# 32minboard.net
KiCad netlist of a schematic drawn in Altium Designer
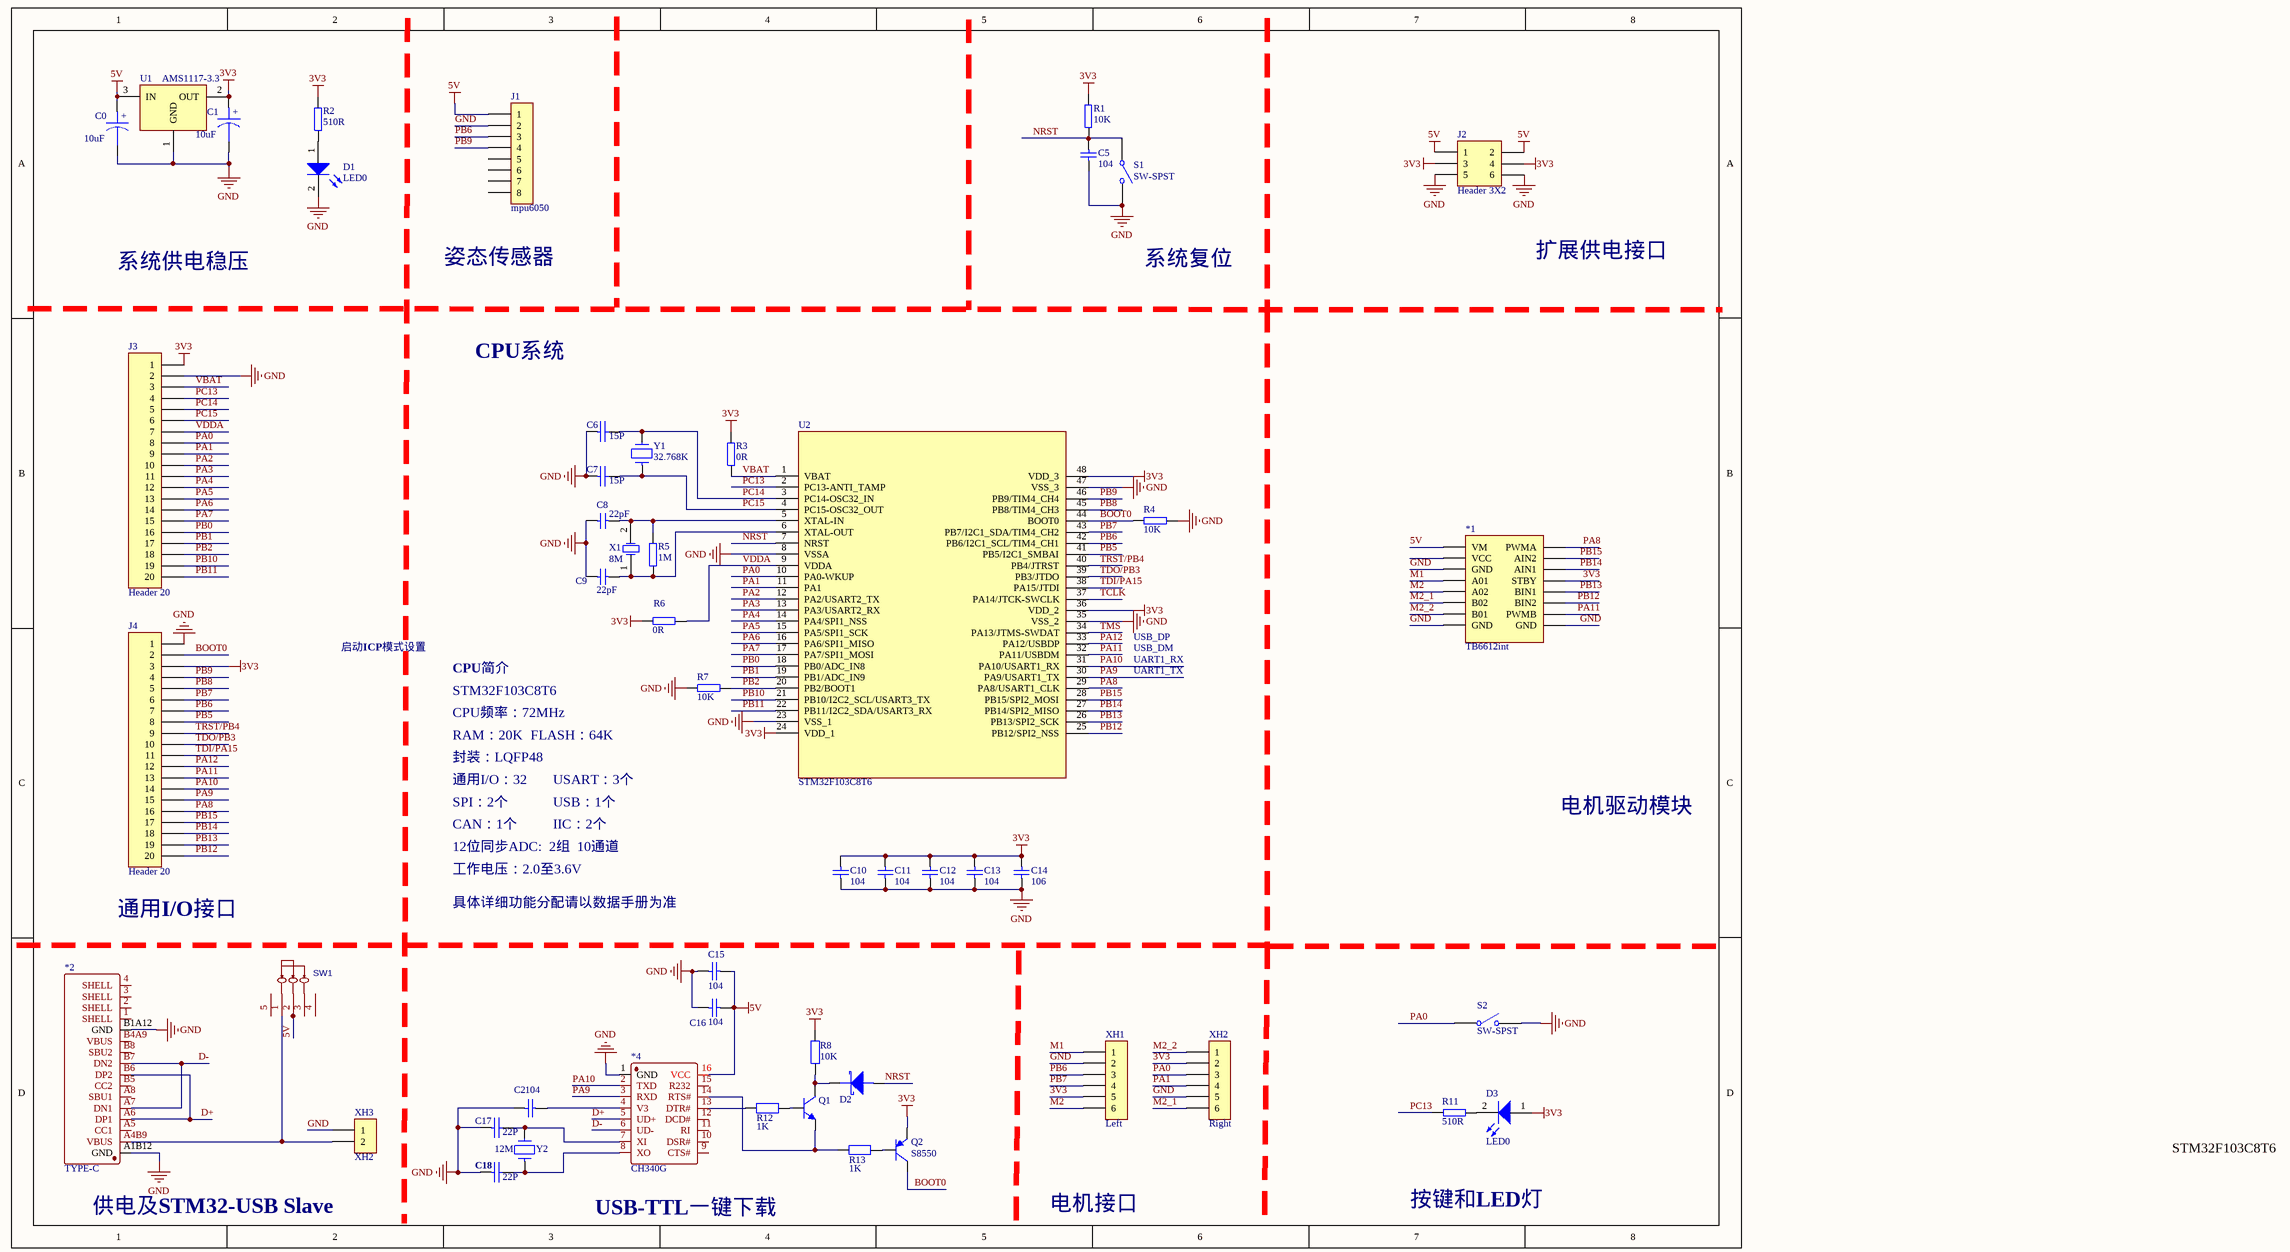
[diagram p0: 32minboard.SchDoc]

(export (version "E")
  (design (tool "Eeschema 10.0.6"))
  (components
    (comp (ref "*1")
      (value "TB6612int")
      (footprint "TB6612int")
      (libsource (lib "General") (part "TB6612int"))
    )
    (comp (ref "*2") (value "TYPE-C") (footprint "TYPE-C") (libsource (lib "General") (part "TYPE-C")))
    (comp (ref "*4")
      (value "CH340G")
      (footprint "SOIC-16_L9.9-W3.9-P1.27-LS6.0-BR")
      (libsource (lib "General") (part "CH340G"))
    )
    (comp (ref "C0")
      (value "10uF")
      (footprint "CAP-TANTALUM-A")
      (description "Capacitor")
      (libsource (lib "*") (part "CAPACITOR POL"))
    )
    (comp (ref "C1")
      (value "10uF")
      (footprint "CAP-TANTALUM-A")
      (description "Capacitor")
      (libsource (lib "*") (part "CAPACITOR POL"))
    )
    (comp (ref "C2")
      (value "104")
      (footprint "0603")
      (description "Capacitor")
      (libsource (lib "Miscellaneous Devices") (part "Cap"))
    )
    (comp (ref "C5")
      (value "104")
      (footprint "0603")
      (description "Capacitor")
      (fields (field (name "PUBLISHER") "ZL_A0OFFICE"))
      (libsource (lib "CommomDevices") (part "CAP1"))
    )
    (comp (ref "C6") (value "15P") (footprint "0603") (libsource (lib "*") (part "CAP")))
    (comp (ref "C7") (value "15P") (footprint "0603") (libsource (lib "*") (part "CAP")))
    (comp (ref "C8")
      (value "22pF")
      (footprint "0603")
      (description "Capacitor")
      (fields (field (name "PUBLISHER") "ZL_A0OFFICE"))
      (libsource (lib "CommomDevices") (part "CAP1"))
    )
    (comp (ref "C9")
      (value "22pF")
      (footprint "0603")
      (description "Capacitor")
      (fields (field (name "PUBLISHER") "ZL_A0OFFICE"))
      (libsource (lib "CommomDevices") (part "CAP1"))
    )
    (comp (ref "C10")
      (value "104")
      (footprint "0603")
      (description "Capacitor")
      (fields (field (name "PUBLISHER") "ZL_A0OFFICE"))
      (libsource (lib "CommomDevices") (part "CAP1"))
    )
    (comp (ref "C11")
      (value "104")
      (footprint "0603")
      (description "Capacitor")
      (fields (field (name "PUBLISHER") "ZL_A0OFFICE"))
      (libsource (lib "CommomDevices") (part "CAP1"))
    )
    (comp (ref "C12")
      (value "104")
      (footprint "0603")
      (description "Capacitor")
      (fields (field (name "PUBLISHER") "ZL_A0OFFICE"))
      (libsource (lib "CommomDevices") (part "CAP1"))
    )
    (comp (ref "C13")
      (value "104")
      (footprint "0603")
      (description "Capacitor")
      (fields (field (name "PUBLISHER") "ZL_A0OFFICE"))
      (libsource (lib "CommomDevices") (part "CAP1"))
    )
    (comp (ref "C14")
      (value "106")
      (footprint "0603")
      (description "Capacitor")
      (fields (field (name "PUBLISHER") "ZL_A0OFFICE"))
      (libsource (lib "CommomDevices") (part "CAP1"))
    )
    (comp (ref "C15")
      (value "104")
      (footprint "0603")
      (description "Capacitor")
      (libsource (lib "Miscellaneous Devices") (part "Cap"))
    )
    (comp (ref "C16")
      (value "104")
      (footprint "0603")
      (description "Capacitor")
      (libsource (lib "Miscellaneous Devices") (part "Cap"))
    )
    (comp (ref "C17") (value "22P") (footprint "0603") (libsource (lib "*") (part "CAP")))
    (comp (ref "C18") (value "22P") (footprint "0603") (libsource (lib "*") (part "CAP")))
    (comp (ref "D1")
      (value "LED0")
      (footprint "LED-0805")
      (description "Typical INFRARED GaAs LED")
      (libsource (lib "Miscellaneous Devices") (part "LED0"))
    )
    (comp (ref "D2")
      (value "DIODE SCHOTTKY")
      (footprint "LL34")
      (description "肖特基二极管")
      (libsource (lib "二极管") (part "DIODE SCHOTTKY"))
    )
    (comp (ref "D3")
      (value "LED0")
      (footprint "LED-0805")
      (description "Typical INFRARED GaAs LED")
      (libsource (lib "Miscellaneous Devices") (part "LED0"))
    )
    (comp (ref "J1")
      (value "mpu6050")
      (footprint "PIN-8-2.54-1.0")
      (description "Connector")
      (libsource (lib "General") (part "HDR1x8"))
    )
    (comp (ref "J2")
      (value "Header 3X2")
      (footprint "PIN-2x3-2.54-1.0")
      (description "Header, 3-Pin, Dual row")
      (fields (field (name "PUBLISHER") "Altium Limited"))
      (libsource (lib "Miscellaneous Connectors") (part "Header 3X2"))
    )
    (comp (ref "J3")
      (value "Header 20")
      (footprint "PIN-20-2.54-1.0")
      (description "Header, 20-Pin")
      (fields (field (name "PUBLISHER") "Altium Limited"))
      (libsource (lib "Miscellaneous Connectors") (part "Header 20"))
    )
    (comp (ref "J4")
      (value "Header 20")
      (footprint "PIN-20-2.54-1.0")
      (description "Header, 20-Pin")
      (fields (field (name "PUBLISHER") "Altium Limited"))
      (libsource (lib "Miscellaneous Connectors") (part "Header 20"))
    )
    (comp (ref "Q1")
      (value "MMBT2222A")
      (footprint "SOT-23")
      (description "NPN Bipolar Transistor")
      (libsource (lib "General") (part "MMBT2222A"))
    )
    (comp (ref "Q2")
      (value "S8550")
      (footprint "SOT-23")
      (description "NPN Bipolar Transistor")
      (libsource (lib "General") (part "PNP"))
    )
    (comp (ref "R1") (value "10K") (footprint "0603") (libsource (lib "ZIBO V2.0_Main") (part "R")))
    (comp (ref "R2") (value "510R") (footprint "0603") (libsource (lib "ZIBO V2.0_Main") (part "R")))
    (comp (ref "R3") (value "0R") (footprint "0603") (libsource (lib "ZIBO V2.0_Main") (part "R")))
    (comp (ref "R4") (value "10K") (footprint "0603") (libsource (lib "ZIBO V2.0_Main") (part "R")))
    (comp (ref "R5") (value "1M") (footprint "0603") (libsource (lib "ZIBO V2.0_Main") (part "R")))
    (comp (ref "R6") (value "0R") (footprint "0603") (libsource (lib "ZIBO V2.0_Main") (part "R")))
    (comp (ref "R7") (value "10K") (footprint "0603") (libsource (lib "ZIBO V2.0_Main") (part "R")))
    (comp (ref "R8")
      (value "10K")
      (footprint "0603")
      (description "Resistor")
      (libsource (lib "") (part "Res2_1"))
    )
    (comp (ref "R11") (value "510R") (footprint "0603") (libsource (lib "ZIBO V2.0_Main") (part "R")))
    (comp (ref "R12")
      (value "1K")
      (footprint "0603")
      (description "Resistor")
      (libsource (lib "Miscellaneous Devices") (part "Res2"))
    )
    (comp (ref "R13")
      (value "1K")
      (footprint "0603")
      (description "Resistor")
      (libsource (lib "Miscellaneous Devices") (part "Res2"))
    )
    (comp (ref "S1")
      (value "SW-SPST")
      (footprint "KEY-SWD-3X4X2")
      (description "Single-Pole, Single-Throw Switch")
      (libsource (lib "Miscellaneous Devices") (part "SW-SPST"))
    )
    (comp (ref "S2")
      (value "SW-SPST")
      (footprint "KEY-SWD-3X4X2")
      (description "Single-Pole, Single-Throw Switch")
      (libsource (lib "Miscellaneous Devices") (part "SW-SPST"))
    )
    (comp (ref "SW1")
      (value "SK12D07VG5")
      (footprint "SW-TH_SK12D07VG5")
      (fields (field (name "BOM_SUPPLIER PART") "C431548") (field (name "CONTRIBUTOR") "LCSC"))
      (libsource (lib "General") (part "SK12D07VG5"))
    )
    (comp (ref "U1")
      (value "AMS1117-3.3")
      (footprint "SOT223")
      (libsource (lib "Newcapec9263_Board_NEW") (part "LT1085CM-3.3"))
    )
    (comp (ref "U2")
      (value "STM32F103C8T6")
      (footprint "QFP-48-0.5")
      (libsource (lib "STM32_Smart") (part "STM32F103C8T6"))
    )
    (comp (ref "X1")
      (value "8M")
      (footprint "OSC HC-49SMD")
      (description "Crystal Oscillator")
      (fields (field (name "PUBLISHER") "ZL_A0OFFICE"))
      (libsource (lib "CommomDevices") (part "XTAL_SMD"))
    )
    (comp (ref "XH1") (value "Left") (footprint "XH6/2.54mm/180") (libsource (lib "XH，VH") (part "XH6")))
    (comp (ref "XH2") (value "Right") (footprint "XH6/2.54mm/180") (libsource (lib "XH，VH") (part "XH6")))
    (comp (ref "XH3") (value "XH2") (footprint "XH2/2.54mm/180") (libsource (lib "XH，VH") (part "XH2")))
    (comp (ref "Y1")
      (value "32.768K")
      (footprint "OSC-3x8-WI-B")
      (description "晶振")
      (libsource (lib "*") (part "CRYSTAL"))
    )
    (comp (ref "Y2")
      (value "12M")
      (footprint "OSC HC-49SMD")
      (description "晶振")
      (libsource (lib "*") (part "CRYSTAL"))
    )
  )
  (nets
    (net (code "1") (name "/BOOT0") (class "Default")
      (node (ref "J4") (pin "2") (pinfunction "2_2") (pintype "passive"))
      (node (ref "Q2") (pin "2") (pinfunction "C_2") (pintype "passive"))
      (node (ref "R4") (pin "2") (pinfunction "2_2") (pintype "passive"))
      (node (ref "U2") (pin "44") (pinfunction "BOOT0_44") (pintype "passive"))
    )
    (net (code "2") (name "/D+") (class "Default")
      (node (ref "*2") (pin "A6") (pinfunction "DP1_A6") (pintype "passive"))
      (node (ref "*2") (pin "B6") (pinfunction "DP2_B6") (pintype "passive"))
      (node (ref "*4") (pin "5") (pinfunction "UD+_5") (pintype "passive"))
    )
    (net (code "3") (name "/D-") (class "Default")
      (node (ref "*2") (pin "A7") (pinfunction "DN1_A7") (pintype "passive"))
      (node (ref "*2") (pin "B7") (pinfunction "DN2_B7") (pintype "passive"))
      (node (ref "*4") (pin "6") (pinfunction "UD-_6") (pintype "passive"))
    )
    (net (code "4") (name "/M1") (class "Default")
      (node (ref "*1") (pin "4") (pinfunction "A01_4") (pintype "passive"))
      (node (ref "XH1") (pin "1") (pinfunction "1_1") (pintype "passive"))
    )
    (net (code "5") (name "/M2") (class "Default")
      (node (ref "*1") (pin "5") (pinfunction "A02_5") (pintype "passive"))
      (node (ref "XH1") (pin "6") (pinfunction "6_6") (pintype "passive"))
    )
    (net (code "6") (name "/M2_1") (class "Default")
      (node (ref "*1") (pin "6") (pinfunction "B02_6") (pintype "passive"))
      (node (ref "XH2") (pin "6") (pinfunction "6_6") (pintype "passive"))
    )
    (net (code "7") (name "/M2_2") (class "Default")
      (node (ref "*1") (pin "7") (pinfunction "B01_7") (pintype "passive"))
      (node (ref "XH2") (pin "1") (pinfunction "1_1") (pintype "passive"))
    )
    (net (code "8") (name "/NRST") (class "Default")
      (node (ref "C5") (pin "1") (pinfunction "1_1") (pintype "passive"))
      (node (ref "D2") (pin "A") (pinfunction "A_A") (pintype "passive"))
      (node (ref "R1") (pin "1") (pinfunction "1_1") (pintype "passive"))
      (node (ref "S1") (pin "1") (pinfunction "COMMON_1") (pintype "passive"))
      (node (ref "U2") (pin "7") (pinfunction "NRST_7") (pintype "passive"))
    )
    (net (code "9") (name "/PA0") (class "Default")
      (node (ref "J3") (pin "8") (pinfunction "8_8") (pintype "passive"))
      (node (ref "S2") (pin "1") (pinfunction "COMMON_1") (pintype "passive"))
      (node (ref "U2") (pin "10") (pinfunction "PA0-WKUP_10") (pintype "passive"))
      (node (ref "XH2") (pin "3") (pinfunction "3_3") (pintype "passive"))
    )
    (net (code "10") (name "/PA1") (class "Default")
      (node (ref "J3") (pin "9") (pinfunction "9_9") (pintype "passive"))
      (node (ref "U2") (pin "11") (pinfunction "PA1_11") (pintype "passive"))
      (node (ref "XH2") (pin "4") (pinfunction "4_4") (pintype "passive"))
    )
    (net (code "11") (name "/PA2") (class "Default")
      (node (ref "J3") (pin "10") (pinfunction "10_10") (pintype "passive"))
      (node (ref "U2") (pin "12") (pinfunction "PA2/USART2_TX_12") (pintype "passive"))
    )
    (net (code "12") (name "/PA3") (class "Default")
      (node (ref "J3") (pin "11") (pinfunction "11_11") (pintype "passive"))
      (node (ref "U2") (pin "13") (pinfunction "PA3/USART2_RX_13") (pintype "passive"))
    )
    (net (code "13") (name "/PA4") (class "Default")
      (node (ref "J3") (pin "12") (pinfunction "12_12") (pintype "passive"))
      (node (ref "U2") (pin "14") (pinfunction "PA4/SPI1_NSS_14") (pintype "passive"))
    )
    (net (code "14") (name "/PA5") (class "Default")
      (node (ref "J3") (pin "13") (pinfunction "13_13") (pintype "passive"))
      (node (ref "U2") (pin "15") (pinfunction "PA5/SPI1_SCK_15") (pintype "passive"))
    )
    (net (code "15") (name "/PA6") (class "Default")
      (node (ref "J3") (pin "14") (pinfunction "14_14") (pintype "passive"))
      (node (ref "U2") (pin "16") (pinfunction "PA6/SPI1_MISO_16") (pintype "passive"))
    )
    (net (code "16") (name "/PA7") (class "Default")
      (node (ref "J3") (pin "15") (pinfunction "15_15") (pintype "passive"))
      (node (ref "U2") (pin "17") (pinfunction "PA7/SPI1_MOSI_17") (pintype "passive"))
    )
    (net (code "17") (name "/PA8") (class "Default")
      (node (ref "*1") (pin "16") (pinfunction "PWMA_16") (pintype "passive"))
      (node (ref "J4") (pin "16") (pinfunction "16_16") (pintype "passive"))
      (node (ref "U2") (pin "29") (pinfunction "PA8/USART1_CLK_29") (pintype "passive"))
    )
    (net (code "18") (name "/PA9") (class "Default")
      (node (ref "*4") (pin "3") (pinfunction "RXD_3") (pintype "passive"))
      (node (ref "J4") (pin "15") (pinfunction "15_15") (pintype "passive"))
      (node (ref "U2") (pin "30") (pinfunction "PA9/USART1_TX_30") (pintype "passive"))
    )
    (net (code "19") (name "/PA10") (class "Default")
      (node (ref "*4") (pin "2") (pinfunction "TXD_2") (pintype "passive"))
      (node (ref "J4") (pin "14") (pinfunction "14_14") (pintype "passive"))
      (node (ref "U2") (pin "31") (pinfunction "PA10/USART1_RX_31") (pintype "passive"))
    )
    (net (code "20") (name "/PA11") (class "Default")
      (node (ref "*1") (pin "10") (pinfunction "PWMB_10") (pintype "passive"))
      (node (ref "J4") (pin "13") (pinfunction "13_13") (pintype "passive"))
      (node (ref "U2") (pin "32") (pinfunction "PA11/USBDM_32") (pintype "passive"))
    )
    (net (code "21") (name "/PA12") (class "Default")
      (node (ref "J4") (pin "12") (pinfunction "12_12") (pintype "passive"))
      (node (ref "U2") (pin "33") (pinfunction "PA12/USBDP_33") (pintype "passive"))
    )
    (net (code "22") (name "/PB0") (class "Default")
      (node (ref "J3") (pin "16") (pinfunction "16_16") (pintype "passive"))
      (node (ref "U2") (pin "18") (pinfunction "PB0/ADC_IN8_18") (pintype "passive"))
    )
    (net (code "23") (name "/PB1") (class "Default")
      (node (ref "J3") (pin "17") (pinfunction "17_17") (pintype "passive"))
      (node (ref "U2") (pin "19") (pinfunction "PB1/ADC_IN9_19") (pintype "passive"))
    )
    (net (code "24") (name "/PB2") (class "Default")
      (node (ref "J3") (pin "18") (pinfunction "18_18") (pintype "passive"))
      (node (ref "R7") (pin "1") (pinfunction "1_1") (pintype "passive"))
      (node (ref "U2") (pin "20") (pinfunction "PB2/BOOT1_20") (pintype "passive"))
    )
    (net (code "25") (name "/PB5") (class "Default")
      (node (ref "J4") (pin "8") (pinfunction "8_8") (pintype "passive"))
      (node (ref "U2") (pin "41") (pinfunction "PB5/I2C1_SMBAI_41") (pintype "passive"))
    )
    (net (code "26") (name "/PB6") (class "Default")
      (node (ref "J1") (pin "3") (pinfunction "3_3") (pintype "passive"))
      (node (ref "J4") (pin "7") (pinfunction "7_7") (pintype "passive"))
      (node (ref "U2") (pin "42") (pinfunction "PB6/I2C1_SCL/TIM4_CH1_42") (pintype "passive"))
      (node (ref "XH1") (pin "3") (pinfunction "3_3") (pintype "passive"))
    )
    (net (code "27") (name "/PB7") (class "Default")
      (node (ref "J4") (pin "6") (pinfunction "6_6") (pintype "passive"))
      (node (ref "U2") (pin "43") (pinfunction "PB7/I2C1_SDA/TIM4_CH2_43") (pintype "passive"))
      (node (ref "XH1") (pin "4") (pinfunction "4_4") (pintype "passive"))
    )
    (net (code "28") (name "/PB8") (class "Default")
      (node (ref "J4") (pin "5") (pinfunction "5_5") (pintype "passive"))
      (node (ref "U2") (pin "45") (pinfunction "PB8/TIM4_CH3_45") (pintype "passive"))
    )
    (net (code "29") (name "/PB9") (class "Default")
      (node (ref "J1") (pin "4") (pinfunction "4_4") (pintype "passive"))
      (node (ref "J4") (pin "4") (pinfunction "4_4") (pintype "passive"))
      (node (ref "U2") (pin "46") (pinfunction "PB9/TIM4_CH4_46") (pintype "passive"))
    )
    (net (code "30") (name "/PB10") (class "Default")
      (node (ref "J3") (pin "19") (pinfunction "19_19") (pintype "passive"))
      (node (ref "U2") (pin "21") (pinfunction "PB10/I2C2_SCL/USART3_TX_21") (pintype "passive"))
    )
    (net (code "31") (name "/PB11") (class "Default")
      (node (ref "J3") (pin "20") (pinfunction "20_20") (pintype "passive"))
      (node (ref "U2") (pin "22") (pinfunction "PB11/I2C2_SDA/USART3_RX_22") (pintype "passive"))
    )
    (net (code "32") (name "/PB12") (class "Default")
      (node (ref "*1") (pin "11") (pinfunction "BIN2_11") (pintype "passive"))
      (node (ref "J4") (pin "20") (pinfunction "20_20") (pintype "passive"))
      (node (ref "U2") (pin "25") (pinfunction "PB12/SPI2_NSS_25") (pintype "passive"))
    )
    (net (code "33") (name "/PB13") (class "Default")
      (node (ref "*1") (pin "12") (pinfunction "BIN1_12") (pintype "passive"))
      (node (ref "J4") (pin "19") (pinfunction "19_19") (pintype "passive"))
      (node (ref "U2") (pin "26") (pinfunction "PB13/SPI2_SCK_26") (pintype "passive"))
    )
    (net (code "34") (name "/PB14") (class "Default")
      (node (ref "*1") (pin "14") (pinfunction "AIN1_14") (pintype "passive"))
      (node (ref "J4") (pin "18") (pinfunction "18_18") (pintype "passive"))
      (node (ref "U2") (pin "27") (pinfunction "PB14/SPI2_MISO_27") (pintype "passive"))
    )
    (net (code "35") (name "/PB15") (class "Default")
      (node (ref "*1") (pin "15") (pinfunction "AIN2_15") (pintype "passive"))
      (node (ref "J4") (pin "17") (pinfunction "17_17") (pintype "passive"))
      (node (ref "U2") (pin "28") (pinfunction "PB15/SPI2_MOSI_28") (pintype "passive"))
    )
    (net (code "36") (name "/PC13") (class "Default")
      (node (ref "J3") (pin "4") (pinfunction "4_4") (pintype "passive"))
      (node (ref "R11") (pin "1") (pinfunction "1_1") (pintype "passive"))
      (node (ref "U2") (pin "2") (pinfunction "PC13-ANTI_TAMP_2") (pintype "passive"))
    )
    (net (code "37") (name "/PC14") (class "Default")
      (node (ref "C6") (pin "2") (pintype "passive"))
      (node (ref "J3") (pin "5") (pinfunction "5_5") (pintype "passive"))
      (node (ref "U2") (pin "3") (pinfunction "PC14-OSC32_IN_3") (pintype "passive"))
      (node (ref "Y1") (pin "2") (pintype "passive"))
    )
    (net (code "38") (name "/PC15") (class "Default")
      (node (ref "C7") (pin "2") (pintype "passive"))
      (node (ref "J3") (pin "6") (pinfunction "6_6") (pintype "passive"))
      (node (ref "U2") (pin "4") (pinfunction "PC15-OSC32_OUT_4") (pintype "passive"))
      (node (ref "Y1") (pin "1") (pintype "passive"))
    )
    (net (code "39") (name "/TCLK") (class "Default")
      (node (ref "U2") (pin "37") (pinfunction "PA14/JTCK-SWCLK_37") (pintype "passive"))
    )
    (net (code "40") (name "/TDI{slash}PA15") (class "Default")
      (node (ref "J4") (pin "11") (pinfunction "11_11") (pintype "passive"))
      (node (ref "U2") (pin "38") (pinfunction "PA15/JTDI_38") (pintype "passive"))
    )
    (net (code "41") (name "/TDO{slash}PB3") (class "Default")
      (node (ref "J4") (pin "10") (pinfunction "10_10") (pintype "passive"))
      (node (ref "U2") (pin "39") (pinfunction "PB3/JTDO_39") (pintype "passive"))
    )
    (net (code "42") (name "/TMS") (class "Default")
      (node (ref "U2") (pin "34") (pinfunction "PA13/JTMS-SWDAT_34") (pintype "passive"))
    )
    (net (code "43") (name "/TRST{slash}PB4") (class "Default")
      (node (ref "J4") (pin "9") (pinfunction "9_9") (pintype "passive"))
      (node (ref "U2") (pin "40") (pinfunction "PB4/JTRST_40") (pintype "passive"))
    )
    (net (code "44") (name "/VBAT") (class "Default")
      (node (ref "J3") (pin "3") (pinfunction "3_3") (pintype "passive"))
      (node (ref "R3") (pin "1") (pinfunction "1_1") (pintype "passive"))
      (node (ref "U2") (pin "1") (pinfunction "VBAT_1") (pintype "passive"))
    )
    (net (code "45") (name "/VDDA") (class "Default")
      (node (ref "J3") (pin "7") (pinfunction "7_7") (pintype "passive"))
      (node (ref "R6") (pin "1") (pinfunction "1_1") (pintype "passive"))
      (node (ref "U2") (pin "9") (pinfunction "VDDA_9") (pintype "passive"))
    )
    (net (code "46") (name "3V3") (class "Default")
      (node (ref "*1") (pin "13") (pinfunction "STBY_13") (pintype "passive"))
      (node (ref "C1") (pin "1") (pinfunction "1_1") (pintype "passive"))
      (node (ref "C10") (pin "1") (pinfunction "1_1") (pintype "passive"))
      (node (ref "C11") (pin "1") (pinfunction "1_1") (pintype "passive"))
      (node (ref "C12") (pin "1") (pinfunction "1_1") (pintype "passive"))
      (node (ref "C13") (pin "1") (pinfunction "1_1") (pintype "passive"))
      (node (ref "C14") (pin "1") (pinfunction "1_1") (pintype "passive"))
      (node (ref "D3") (pin "1") (pinfunction "A_1") (pintype "passive"))
      (node (ref "J2") (pin "3") (pinfunction "3_3") (pintype "passive"))
      (node (ref "J2") (pin "4") (pinfunction "4_4") (pintype "passive"))
      (node (ref "J3") (pin "1") (pinfunction "1_1") (pintype "passive"))
      (node (ref "J4") (pin "3") (pinfunction "3_3") (pintype "passive"))
      (node (ref "Q2") (pin "3") (pinfunction "E_3") (pintype "passive"))
      (node (ref "R1") (pin "2") (pinfunction "2_2") (pintype "passive"))
      (node (ref "R2") (pin "2") (pinfunction "2_2") (pintype "passive"))
      (node (ref "R3") (pin "2") (pinfunction "2_2") (pintype "passive"))
      (node (ref "R6") (pin "2") (pinfunction "2_2") (pintype "passive"))
      (node (ref "R8") (pin "1") (pinfunction "1_1") (pintype "passive"))
      (node (ref "U1") (pin "2") (pinfunction "OUT_2") (pintype "passive"))
      (node (ref "U2") (pin "24") (pinfunction "VDD_1_24") (pintype "passive"))
      (node (ref "U2") (pin "36") (pinfunction "VDD_2_36") (pintype "passive"))
      (node (ref "U2") (pin "48") (pinfunction "VDD_3_48") (pintype "passive"))
      (node (ref "XH1") (pin "5") (pinfunction "5_5") (pintype "passive"))
      (node (ref "XH2") (pin "2") (pinfunction "2_2") (pintype "passive"))
    )
    (net (code "47") (name "5V") (class "Default")
      (node (ref "*1") (pin "1") (pinfunction "VM_1") (pintype "passive"))
      (node (ref "*4") (pin "16") (pinfunction "VCC_16") (pintype "passive"))
      (node (ref "C0") (pin "1") (pinfunction "1_1") (pintype "passive"))
      (node (ref "C15") (pin "1") (pinfunction "1_1") (pintype "passive"))
      (node (ref "C16") (pin "1") (pinfunction "1_1") (pintype "passive"))
      (node (ref "J1") (pin "1") (pinfunction "1_1") (pintype "passive"))
      (node (ref "J2") (pin "1") (pinfunction "1_1") (pintype "passive"))
      (node (ref "J2") (pin "2") (pinfunction "2_2") (pintype "passive"))
      (node (ref "SW1") (pin "2") (pinfunction "2_2") (pintype "passive"))
      (node (ref "U1") (pin "3") (pinfunction "IN_3") (pintype "passive"))
    )
    (net (code "48") (name "GND") (class "Default")
      (node (ref "*1") (pin "3") (pinfunction "GND_3") (pintype "passive"))
      (node (ref "*1") (pin "8") (pinfunction "GND_8") (pintype "passive"))
      (node (ref "*1") (pin "9") (pinfunction "GND_9") (pintype "passive"))
      (node (ref "*2") (pin "A1B12") (pinfunction "GND_A1B12") (pintype "passive"))
      (node (ref "*2") (pin "B1A12") (pinfunction "GND_B1A12") (pintype "passive"))
      (node (ref "*4") (pin "1") (pinfunction "GND_1") (pintype "passive"))
      (node (ref "C0") (pin "2") (pinfunction "2_2") (pintype "passive"))
      (node (ref "C1") (pin "2") (pinfunction "2_2") (pintype "passive"))
      (node (ref "C10") (pin "2") (pinfunction "2_2") (pintype "passive"))
      (node (ref "C11") (pin "2") (pinfunction "2_2") (pintype "passive"))
      (node (ref "C12") (pin "2") (pinfunction "2_2") (pintype "passive"))
      (node (ref "C13") (pin "2") (pinfunction "2_2") (pintype "passive"))
      (node (ref "C14") (pin "2") (pinfunction "2_2") (pintype "passive"))
      (node (ref "C15") (pin "2") (pinfunction "2_2") (pintype "passive"))
      (node (ref "C16") (pin "2") (pinfunction "2_2") (pintype "passive"))
      (node (ref "C17") (pin "1") (pintype "passive"))
      (node (ref "C18") (pin "1") (pintype "passive"))
      (node (ref "C2") (pin "2") (pinfunction "2_2") (pintype "passive"))
      (node (ref "C5") (pin "2") (pinfunction "2_2") (pintype "passive"))
      (node (ref "C6") (pin "1") (pintype "passive"))
      (node (ref "C7") (pin "1") (pintype "passive"))
      (node (ref "C8") (pin "2") (pinfunction "2_2") (pintype "passive"))
      (node (ref "C9") (pin "2") (pinfunction "2_2") (pintype "passive"))
      (node (ref "D1") (pin "2") (pinfunction "K_2") (pintype "passive"))
      (node (ref "J1") (pin "2") (pinfunction "2_2") (pintype "passive"))
      (node (ref "J2") (pin "5") (pinfunction "5_5") (pintype "passive"))
      (node (ref "J2") (pin "6") (pinfunction "6_6") (pintype "passive"))
      (node (ref "J3") (pin "2") (pinfunction "2_2") (pintype "passive"))
      (node (ref "J4") (pin "1") (pinfunction "1_1") (pintype "passive"))
      (node (ref "R4") (pin "1") (pinfunction "1_1") (pintype "passive"))
      (node (ref "R7") (pin "2") (pinfunction "2_2") (pintype "passive"))
      (node (ref "S1") (pin "2") (pinfunction "NO_2") (pintype "passive"))
      (node (ref "S2") (pin "2") (pinfunction "NO_2") (pintype "passive"))
      (node (ref "U1") (pin "1") (pinfunction "GND_1") (pintype "passive"))
      (node (ref "U2") (pin "23") (pinfunction "VSS_1_23") (pintype "passive"))
      (node (ref "U2") (pin "35") (pinfunction "VSS_2_35") (pintype "passive"))
      (node (ref "U2") (pin "47") (pinfunction "VSS_3_47") (pintype "passive"))
      (node (ref "U2") (pin "8") (pinfunction "VSSA_8") (pintype "passive"))
      (node (ref "XH1") (pin "2") (pinfunction "2_2") (pintype "passive"))
      (node (ref "XH2") (pin "5") (pinfunction "5_5") (pintype "passive"))
      (node (ref "XH3") (pin "1") (pinfunction "1_1") (pintype "passive"))
    )
    (net (code "49") (name "Net-(*2-VBUS-PadA4B9)") (class "Default")
      (node (ref "*2") (pin "A4B9") (pinfunction "VBUS_A4B9") (pintype "passive"))
      (node (ref "SW1") (pin "1") (pinfunction "1_1") (pintype "passive"))
      (node (ref "XH3") (pin "2") (pinfunction "2_2") (pintype "passive"))
    )
    (net (code "50") (name "Net-(*4-DTR#)") (class "Default")
      (node (ref "*4") (pin "13") (pinfunction "DTR#_13") (pintype "passive"))
      (node (ref "R12") (pin "2") (pinfunction "2_2") (pintype "passive"))
    )
    (net (code "51") (name "Net-(*4-RTS#)") (class "Default")
      (node (ref "*4") (pin "14") (pinfunction "RTS#_14") (pintype "passive"))
      (node (ref "Q1") (pin "2") (pinfunction "E_2") (pintype "passive"))
      (node (ref "R13") (pin "2") (pinfunction "2_2") (pintype "passive"))
    )
    (net (code "52") (name "Net-(*4-V3)") (class "Default")
      (node (ref "*4") (pin "4") (pinfunction "V3_4") (pintype "passive"))
      (node (ref "C2") (pin "1") (pinfunction "1_1") (pintype "passive"))
    )
    (net (code "53") (name "Net-(*4-XI)") (class "Default")
      (node (ref "*4") (pin "7") (pinfunction "XI_7") (pintype "passive"))
      (node (ref "C17") (pin "2") (pintype "passive"))
      (node (ref "Y2") (pin "2") (pintype "passive"))
    )
    (net (code "54") (name "Net-(*4-XO)") (class "Default")
      (node (ref "*4") (pin "8") (pinfunction "XO_8") (pintype "passive"))
      (node (ref "C18") (pin "2") (pintype "passive"))
      (node (ref "Y2") (pin "1") (pintype "passive"))
    )
    (net (code "55") (name "Net-(D1-A)") (class "Default")
      (node (ref "D1") (pin "1") (pinfunction "A_1") (pintype "passive"))
      (node (ref "R2") (pin "1") (pinfunction "1_1") (pintype "passive"))
    )
    (net (code "56") (name "Net-(D3-K)") (class "Default")
      (node (ref "D3") (pin "2") (pinfunction "K_2") (pintype "passive"))
      (node (ref "R11") (pin "2") (pinfunction "2_2") (pintype "passive"))
    )
    (net (code "57") (name "Net-(Q1-B)") (class "Default")
      (node (ref "Q1") (pin "1") (pinfunction "B_1") (pintype "passive"))
      (node (ref "R12") (pin "1") (pinfunction "1_1") (pintype "passive"))
    )
    (net (code "58") (name "Net-(Q1-C)") (class "Default")
      (node (ref "D2") (pin "K") (pinfunction "K_K") (pintype "passive"))
      (node (ref "Q1") (pin "3") (pinfunction "C_3") (pintype "passive"))
      (node (ref "R8") (pin "2") (pinfunction "2_2") (pintype "passive"))
    )
    (net (code "59") (name "Net-(Q2-B)") (class "Default")
      (node (ref "Q2") (pin "1") (pinfunction "B_1") (pintype "passive"))
      (node (ref "R13") (pin "1") (pinfunction "1_1") (pintype "passive"))
    )
    (net (code "60") (name "Net-(U2-XTAL-IN)") (class "Default")
      (node (ref "C8") (pin "1") (pinfunction "1_1") (pintype "passive"))
      (node (ref "R5") (pin "2") (pinfunction "2_2") (pintype "passive"))
      (node (ref "U2") (pin "5") (pinfunction "XTAL-IN_5") (pintype "passive"))
      (node (ref "X1") (pin "2") (pinfunction "2_2") (pintype "passive"))
    )
    (net (code "61") (name "Net-(U2-XTAL-OUT)") (class "Default")
      (node (ref "C9") (pin "1") (pinfunction "1_1") (pintype "passive"))
      (node (ref "R5") (pin "1") (pinfunction "1_1") (pintype "passive"))
      (node (ref "U2") (pin "6") (pinfunction "XTAL-OUT_6") (pintype "passive"))
      (node (ref "X1") (pin "1") (pinfunction "1_1") (pintype "passive"))
    )
    (net (code "62") (name "unconnected-(*1-VCC-Pad2)") (class "Default")
      (node (ref "*1") (pin "2") (pinfunction "VCC_2") (pintype "passive"))
    )
    (net (code "63") (name "unconnected-(*2-CC1-PadA5)") (class "Default")
      (node (ref "*2") (pin "A5") (pinfunction "CC1_A5") (pintype "passive"))
    )
    (net (code "64") (name "unconnected-(*2-CC2-PadB5)") (class "Default")
      (node (ref "*2") (pin "B5") (pinfunction "CC2_B5") (pintype "passive"))
    )
    (net (code "65") (name "unconnected-(*2-SBU1-PadA8)") (class "Default")
      (node (ref "*2") (pin "A8") (pinfunction "SBU1_A8") (pintype "passive"))
    )
    (net (code "66") (name "unconnected-(*2-SBU2-PadB8)") (class "Default")
      (node (ref "*2") (pin "B8") (pinfunction "SBU2_B8") (pintype "passive"))
    )
    (net (code "67") (name "unconnected-(*2-SHELL-Pad1)") (class "Default")
      (node (ref "*2") (pin "1") (pinfunction "SHELL_1") (pintype "passive"))
    )
    (net (code "68") (name "unconnected-(*2-SHELL-Pad2)") (class "Default")
      (node (ref "*2") (pin "2") (pinfunction "SHELL_2") (pintype "passive"))
    )
    (net (code "69") (name "unconnected-(*2-SHELL-Pad3)") (class "Default")
      (node (ref "*2") (pin "3") (pinfunction "SHELL_3") (pintype "passive"))
    )
    (net (code "70") (name "unconnected-(*2-SHELL-Pad4)") (class "Default")
      (node (ref "*2") (pin "4") (pinfunction "SHELL_4") (pintype "passive"))
    )
    (net (code "71") (name "unconnected-(*2-VBUS-PadB4A9)") (class "Default")
      (node (ref "*2") (pin "B4A9") (pinfunction "VBUS_B4A9") (pintype "passive"))
    )
    (net (code "72") (name "unconnected-(*4-CTS#-Pad9)") (class "Default")
      (node (ref "*4") (pin "9") (pinfunction "CTS#_9") (pintype "passive"))
    )
    (net (code "73") (name "unconnected-(*4-DCD#-Pad12)") (class "Default")
      (node (ref "*4") (pin "12") (pinfunction "DCD#_12") (pintype "passive"))
    )
    (net (code "74") (name "unconnected-(*4-DSR#-Pad10)") (class "Default")
      (node (ref "*4") (pin "10") (pinfunction "DSR#_10") (pintype "passive"))
    )
    (net (code "75") (name "unconnected-(*4-R232-Pad15)") (class "Default")
      (node (ref "*4") (pin "15") (pinfunction "R232_15") (pintype "passive"))
    )
    (net (code "76") (name "unconnected-(*4-RI-Pad11)") (class "Default")
      (node (ref "*4") (pin "11") (pinfunction "RI_11") (pintype "passive"))
    )
    (net (code "77") (name "unconnected-(J1-Pad5)") (class "Default")
      (node (ref "J1") (pin "5") (pinfunction "5_5") (pintype "passive"))
    )
    (net (code "78") (name "unconnected-(J1-Pad6)") (class "Default")
      (node (ref "J1") (pin "6") (pinfunction "6_6") (pintype "passive"))
    )
    (net (code "79") (name "unconnected-(J1-Pad7)") (class "Default")
      (node (ref "J1") (pin "7") (pinfunction "7_7") (pintype "passive"))
    )
    (net (code "80") (name "unconnected-(J1-Pad8)") (class "Default")
      (node (ref "J1") (pin "8") (pinfunction "8_8") (pintype "passive"))
    )
    (net (code "81") (name "unconnected-(SW1-Pad3)") (class "Default")
      (node (ref "SW1") (pin "3") (pinfunction "3_3") (pintype "passive"))
    )
    (net (code "82") (name "unconnected-(SW1-Pad4)") (class "Default")
      (node (ref "SW1") (pin "4") (pinfunction "4_4") (pintype "passive"))
    )
    (net (code "83") (name "unconnected-(SW1-Pad5)") (class "Default")
      (node (ref "SW1") (pin "5") (pinfunction "5_5") (pintype "passive"))
    )
  )
)
